# DieuKhienThietBiWinForm.net
KiCad netlist of a schematic drawn in Altium Designer
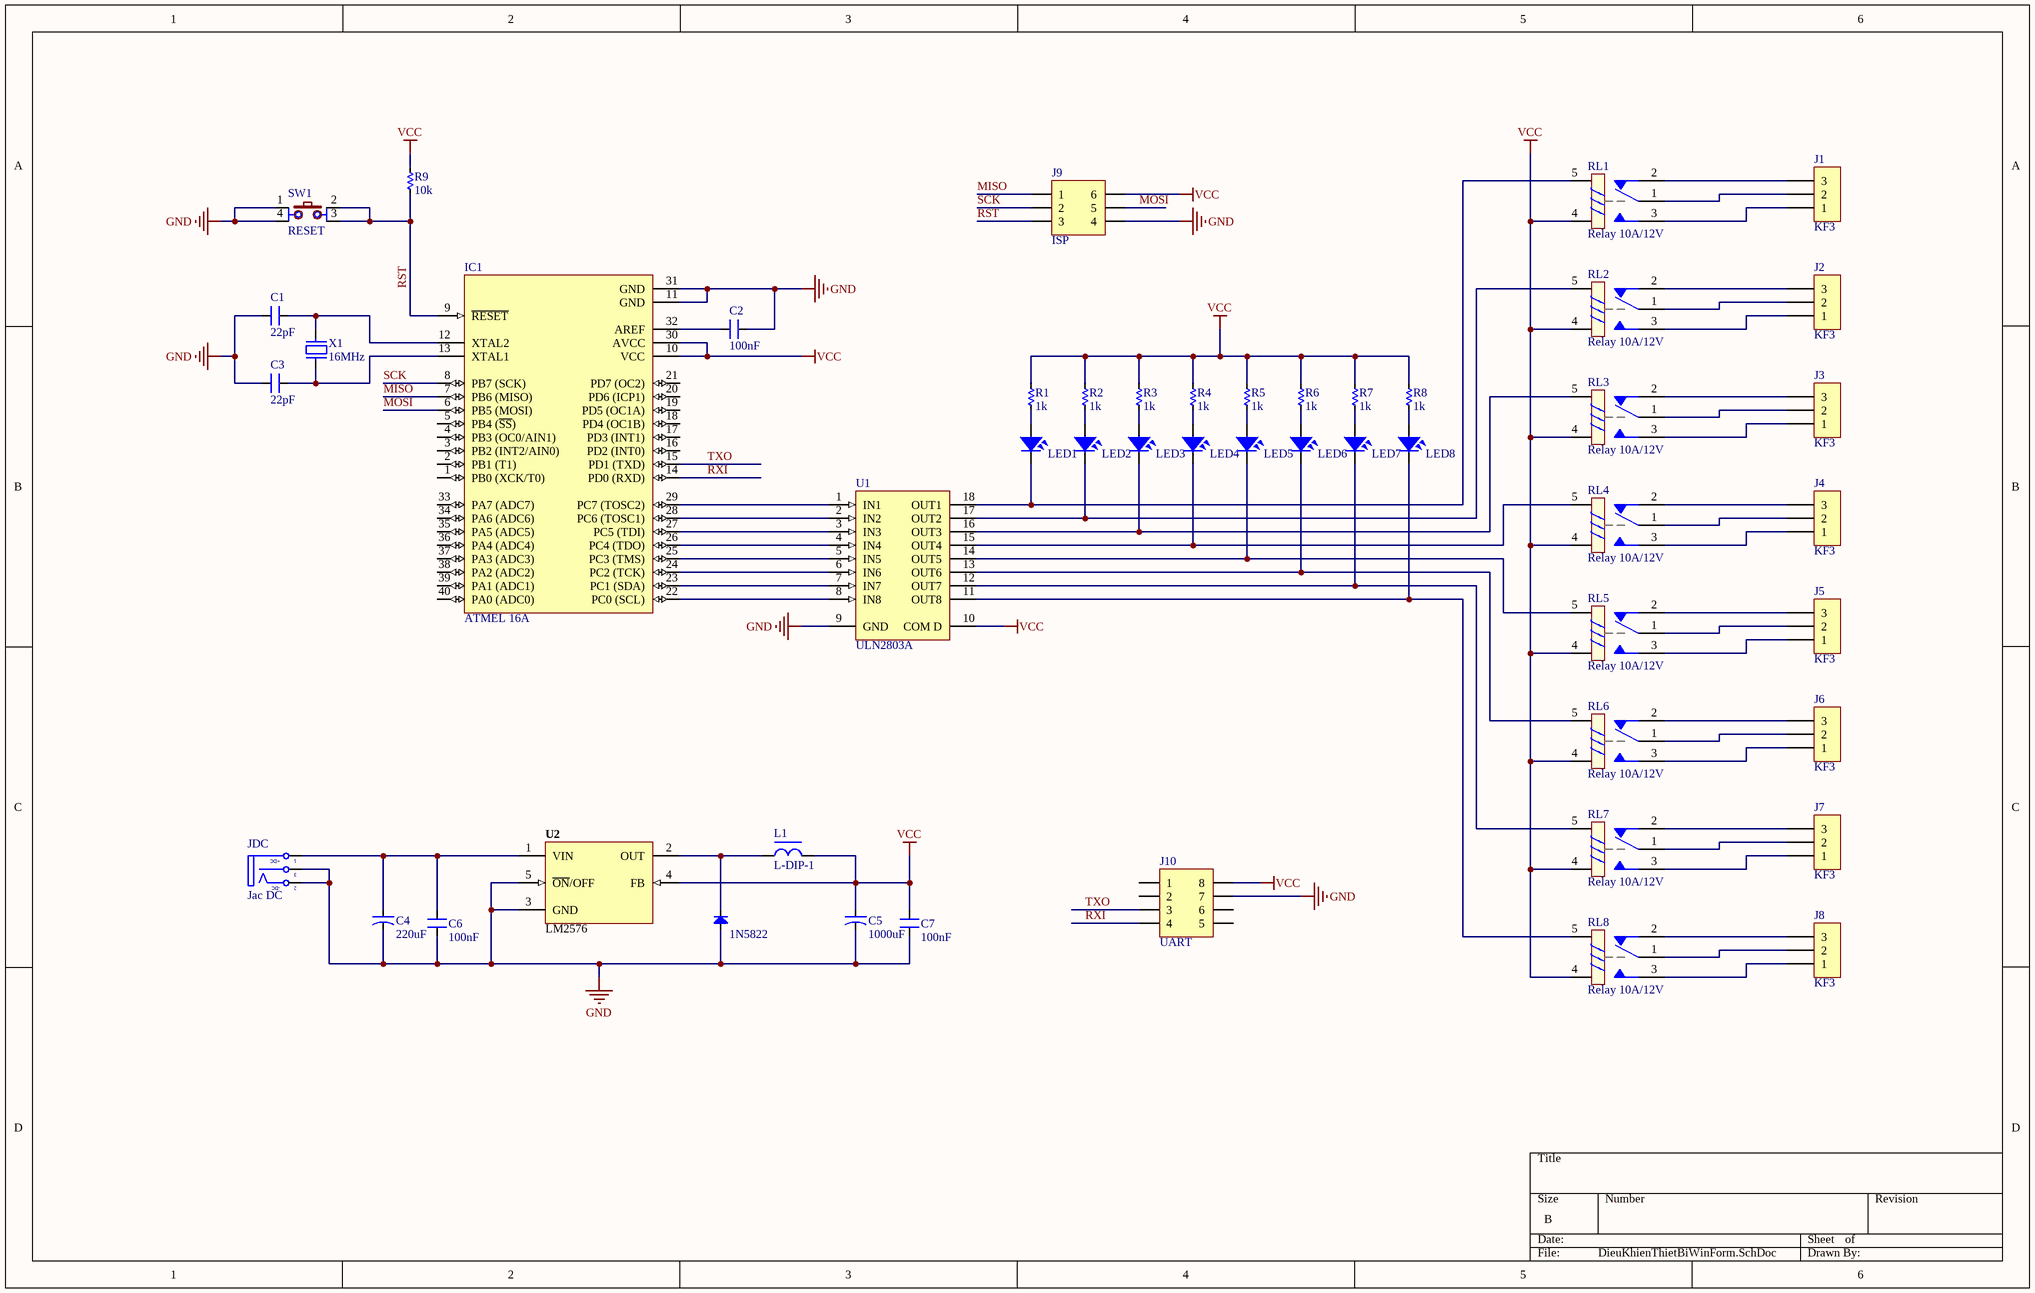
[diagram p0: DieuKhienThietBiWinForm.SchDoc]

(export (version "E")
  (design (tool "Eeschema 10.0.6"))
  (components
    (comp (ref "1N5822")
      (value "Diode")
      (footprint "DIO-5A")
      (description "Default Diode")
      (fields (field (name "PUBLISHER") "Altium Limited"))
      (libsource (lib "LIBRARY") (part "Diode"))
    )
    (comp (ref "C1") (value "22pF") (footprint "CN1.5") (libsource (lib "LIBRARY") (part "CN")))
    (comp (ref "C2") (value "100nF") (footprint "CN1.5") (libsource (lib "LIBRARY") (part "CN")))
    (comp (ref "C3") (value "22pF") (footprint "CN1.5") (libsource (lib "LIBRARY") (part "CN")))
    (comp (ref "C4")
      (value "220uF")
      (footprint "CA-ALU-8")
      (description "Capacitor (Semiconductor SIM Model)")
      (fields (field (name "PUBLISHER") "Altium Limited"))
      (libsource (lib "LIBRARY") (part "CN-ALU-DIP"))
    )
    (comp (ref "C5")
      (value "1000uF")
      (footprint "CA-ALU-10")
      (description "Capacitor (Semiconductor SIM Model)")
      (fields (field (name "PUBLISHER") "Altium Limited"))
      (libsource (lib "LIBRARY") (part "CN-ALU-DIP"))
    )
    (comp (ref "C6") (value "100nF") (footprint "CN1.5") (libsource (lib "LIBRARY") (part "CN")))
    (comp (ref "C7") (value "100nF") (footprint "CN1.5") (libsource (lib "LIBRARY") (part "CN")))
    (comp (ref "IC1")
      (value "ATMEL 16A")
      (footprint "DIP40/W0.6")
      (description "8-Bit AVR Microcontroller with 16K Bytes of In-System Programmable Flash Memory")
      (libsource (lib "LIBRARY") (part "ATmega16A-PU"))
    )
    (comp (ref "J1")
      (value "KF3")
      (footprint "KF3-5.08")
      (fields
        (field (name "MANUFACTURER") "Würth Elektronik eiSos GmbH")
        (field (name "PARTNO") "691103110003")
        (field (name "CREATED BY") "Karrer Zheng")
      )
      (libsource (lib "LIBRARY") (part "KF3"))
    )
    (comp (ref "J2")
      (value "KF3")
      (footprint "KF3-5.08")
      (fields
        (field (name "MANUFACTURER") "Würth Elektronik eiSos GmbH")
        (field (name "PARTNO") "691103110003")
        (field (name "CREATED BY") "Karrer Zheng")
      )
      (libsource (lib "LIBRARY") (part "KF3"))
    )
    (comp (ref "J3")
      (value "KF3")
      (footprint "KF3-5.08")
      (fields
        (field (name "MANUFACTURER") "Würth Elektronik eiSos GmbH")
        (field (name "PARTNO") "691103110003")
        (field (name "CREATED BY") "Karrer Zheng")
      )
      (libsource (lib "LIBRARY") (part "KF3"))
    )
    (comp (ref "J4")
      (value "KF3")
      (footprint "KF3-5.08")
      (fields
        (field (name "MANUFACTURER") "Würth Elektronik eiSos GmbH")
        (field (name "PARTNO") "691103110003")
        (field (name "CREATED BY") "Karrer Zheng")
      )
      (libsource (lib "LIBRARY") (part "KF3"))
    )
    (comp (ref "J5")
      (value "KF3")
      (footprint "KF3-5.08")
      (fields
        (field (name "MANUFACTURER") "Würth Elektronik eiSos GmbH")
        (field (name "PARTNO") "691103110003")
        (field (name "CREATED BY") "Karrer Zheng")
      )
      (libsource (lib "LIBRARY") (part "KF3"))
    )
    (comp (ref "J6")
      (value "KF3")
      (footprint "KF3-5.08")
      (fields
        (field (name "MANUFACTURER") "Würth Elektronik eiSos GmbH")
        (field (name "PARTNO") "691103110003")
        (field (name "CREATED BY") "Karrer Zheng")
      )
      (libsource (lib "LIBRARY") (part "KF3"))
    )
    (comp (ref "J7")
      (value "KF3")
      (footprint "KF3-5.08")
      (fields
        (field (name "MANUFACTURER") "Würth Elektronik eiSos GmbH")
        (field (name "PARTNO") "691103110003")
        (field (name "CREATED BY") "Karrer Zheng")
      )
      (libsource (lib "LIBRARY") (part "KF3"))
    )
    (comp (ref "J8")
      (value "KF3")
      (footprint "KF3-5.08")
      (fields
        (field (name "MANUFACTURER") "Würth Elektronik eiSos GmbH")
        (field (name "PARTNO") "691103110003")
        (field (name "CREATED BY") "Karrer Zheng")
      )
      (libsource (lib "LIBRARY") (part "KF3"))
    )
    (comp (ref "J9")
      (value "ISP")
      (footprint "JP3-D2T")
      (description "WR-PHD 2.54 mm Dual Socket Header")
      (fields
        (field (name "MANUFACTURER") "Würth Elektronik eiSos GmbH")
        (field (name "PARTNO") "61300621821")
        (field (name "CREATED BY") "Karrer Zheng")
      )
      (libsource (lib "LIBRARY") (part "JP3x2"))
    )
    (comp (ref "J10")
      (value "UART")
      (footprint "JP4-D2T")
      (description "WR-PHD 2.54 mm Dual Socket Header")
      (fields
        (field (name "MANUFACTURER") "Würth Elektronik eiSos GmbH")
        (field (name "PARTNO") "61300821821")
        (field (name "CREATED BY") "Karrer Zheng")
      )
      (libsource (lib "LIBRARY") (part "JP4x2"))
    )
    (comp (ref "JDC")
      (value "Jac DC")
      (footprint "DC0")
      (description "Jac DC input")
      (libsource (lib "LIBRARY") (part "DCIN"))
    )
    (comp (ref "L1")
      (value "L-DIP-1")
      (footprint "L-DIP-M-8")
      (description "Inductor")
      (libsource (lib "LIBRARY") (part "L-DIP-1"))
    )
    (comp (ref "LED1")
      (value "LED")
      (footprint "LED-5-RED")
      (description "LED Single colour Green and Red")
      (libsource (lib "LIBRARY") (part "LED"))
    )
    (comp (ref "LED2")
      (value "LED")
      (footprint "LED-5-RED")
      (description "LED Single colour Green and Red")
      (libsource (lib "LIBRARY") (part "LED"))
    )
    (comp (ref "LED3")
      (value "LED")
      (footprint "LED-5-RED")
      (description "LED Single colour Green and Red")
      (libsource (lib "LIBRARY") (part "LED"))
    )
    (comp (ref "LED4")
      (value "LED")
      (footprint "LED-5-RED")
      (description "LED Single colour Green and Red")
      (libsource (lib "LIBRARY") (part "LED"))
    )
    (comp (ref "LED5")
      (value "LED")
      (footprint "LED-5-RED")
      (description "LED Single colour Green and Red")
      (libsource (lib "LIBRARY") (part "LED"))
    )
    (comp (ref "LED6")
      (value "LED")
      (footprint "LED-5-RED")
      (description "LED Single colour Green and Red")
      (libsource (lib "LIBRARY") (part "LED"))
    )
    (comp (ref "LED7")
      (value "LED")
      (footprint "LED-5-RED")
      (description "LED Single colour Green and Red")
      (libsource (lib "LIBRARY") (part "LED"))
    )
    (comp (ref "LED8")
      (value "LED")
      (footprint "LED-5-RED")
      (description "LED Single colour Green and Red")
      (libsource (lib "LIBRARY") (part "LED"))
    )
    (comp (ref "R1")
      (value "1k")
      (footprint "RES-1/2W")
      (description "Res")
      (fields
        (field (name "MANUFACTURER") "Generic Components")
        (field (name "PUBLISHER") "Altium Hobart Technology Centre")
      )
      (libsource (lib "LIBRARY") (part "Res"))
    )
    (comp (ref "R2")
      (value "1k")
      (footprint "RES-1/2W")
      (description "Res")
      (fields
        (field (name "MANUFACTURER") "Generic Components")
        (field (name "PUBLISHER") "Altium Hobart Technology Centre")
      )
      (libsource (lib "LIBRARY") (part "Res"))
    )
    (comp (ref "R3")
      (value "1k")
      (footprint "RES-1/2W")
      (description "Res")
      (fields
        (field (name "MANUFACTURER") "Generic Components")
        (field (name "PUBLISHER") "Altium Hobart Technology Centre")
      )
      (libsource (lib "LIBRARY") (part "Res"))
    )
    (comp (ref "R4")
      (value "1k")
      (footprint "RES-1/2W")
      (description "Res")
      (fields
        (field (name "MANUFACTURER") "Generic Components")
        (field (name "PUBLISHER") "Altium Hobart Technology Centre")
      )
      (libsource (lib "LIBRARY") (part "Res"))
    )
    (comp (ref "R5")
      (value "1k")
      (footprint "RES-1/2W")
      (description "Res")
      (fields
        (field (name "MANUFACTURER") "Generic Components")
        (field (name "PUBLISHER") "Altium Hobart Technology Centre")
      )
      (libsource (lib "LIBRARY") (part "Res"))
    )
    (comp (ref "R6")
      (value "1k")
      (footprint "RES-1/2W")
      (description "Res")
      (fields
        (field (name "MANUFACTURER") "Generic Components")
        (field (name "PUBLISHER") "Altium Hobart Technology Centre")
      )
      (libsource (lib "LIBRARY") (part "Res"))
    )
    (comp (ref "R7")
      (value "1k")
      (footprint "RES-1/2W")
      (description "Res")
      (fields
        (field (name "MANUFACTURER") "Generic Components")
        (field (name "PUBLISHER") "Altium Hobart Technology Centre")
      )
      (libsource (lib "LIBRARY") (part "Res"))
    )
    (comp (ref "R8")
      (value "1k")
      (footprint "RES-1/2W")
      (description "Res")
      (fields
        (field (name "MANUFACTURER") "Generic Components")
        (field (name "PUBLISHER") "Altium Hobart Technology Centre")
      )
      (libsource (lib "LIBRARY") (part "Res"))
    )
    (comp (ref "R9")
      (value "10k")
      (footprint "RES-1/2W")
      (description "Res")
      (fields
        (field (name "MANUFACTURER") "Generic Components")
        (field (name "PUBLISHER") "Altium Hobart Technology Centre")
      )
      (libsource (lib "LIBRARY") (part "Res"))
    )
    (comp (ref "RL1")
      (value "Relay 10A/12V")
      (footprint "RELAY 5")
      (description "Relay SPDT,10A - 12VDC 5 Pin")
      (libsource (lib "LIBRARY") (part "Relay 5"))
    )
    (comp (ref "RL2")
      (value "Relay 10A/12V")
      (footprint "RELAY 5")
      (description "Relay SPDT,10A - 12VDC 5 Pin")
      (libsource (lib "LIBRARY") (part "Relay 5"))
    )
    (comp (ref "RL3")
      (value "Relay 10A/12V")
      (footprint "RELAY 5")
      (description "Relay SPDT,10A - 12VDC 5 Pin")
      (libsource (lib "LIBRARY") (part "Relay 5"))
    )
    (comp (ref "RL4")
      (value "Relay 10A/12V")
      (footprint "RELAY 5")
      (description "Relay SPDT,10A - 12VDC 5 Pin")
      (libsource (lib "LIBRARY") (part "Relay 5"))
    )
    (comp (ref "RL5")
      (value "Relay 10A/12V")
      (footprint "RELAY 5")
      (description "Relay SPDT,10A - 12VDC 5 Pin")
      (libsource (lib "LIBRARY") (part "Relay 5"))
    )
    (comp (ref "RL6")
      (value "Relay 10A/12V")
      (footprint "RELAY 5")
      (description "Relay SPDT,10A - 12VDC 5 Pin")
      (libsource (lib "LIBRARY") (part "Relay 5"))
    )
    (comp (ref "RL7")
      (value "Relay 10A/12V")
      (footprint "RELAY 5")
      (description "Relay SPDT,10A - 12VDC 5 Pin")
      (libsource (lib "LIBRARY") (part "Relay 5"))
    )
    (comp (ref "RL8")
      (value "Relay 10A/12V")
      (footprint "RELAY 5")
      (description "Relay SPDT,10A - 12VDC 5 Pin")
      (libsource (lib "LIBRARY") (part "Relay 5"))
    )
    (comp (ref "SW1")
      (value "RESET")
      (footprint "SW2-DIP")
      (description "Switch button 4 pin")
      (libsource (lib "LIBRARY") (part "SW4"))
    )
    (comp (ref "U1")
      (value "ULN2803A")
      (footprint "DIP18")
      (description "High-Voltage, High-Current Darlington Array")
      (fields (field (name "PUBLISHER") "Altium Limited"))
      (libsource (lib "LIBRARY") (part "ULN2803A"))
    )
    (comp (ref "U2") (value "LM2576") (footprint "DIP5") (libsource (lib "LIBRARY") (part "LM2576")))
    (comp (ref "X1")
      (value "16MHz")
      (footprint "XT2")
      (description "Crystal, 32.768 KHz, -40 to 85 degC, 3.2 x 1.5 x 0.9 mm SMD")
      (libsource (lib "LIBRARY") (part "XT2"))
    )
  )
  (nets
    (net (code "1") (name "/MISO") (class "Default")
      (node (ref "IC1") (pin "7") (pinfunction "PB6_(MISO)_7") (pintype "bidirectional"))
      (node (ref "J9") (pin "1") (pinfunction "1_1") (pintype "passive"))
    )
    (net (code "2") (name "/MOSI") (class "Default")
      (node (ref "IC1") (pin "6") (pinfunction "PB5_(MOSI)_6") (pintype "bidirectional"))
      (node (ref "J9") (pin "5") (pinfunction "5_5") (pintype "passive"))
    )
    (net (code "3") (name "/RST") (class "Default")
      (node (ref "IC1") (pin "9") (pinfunction "~{RESET}_9") (pintype "input"))
      (node (ref "J9") (pin "3") (pinfunction "3_3") (pintype "passive"))
      (node (ref "R9") (pin "1") (pinfunction "1_1") (pintype "passive"))
      (node (ref "SW1") (pin "2") (pinfunction "2_2") (pintype "passive"))
      (node (ref "SW1") (pin "3") (pinfunction "3_3") (pintype "passive"))
    )
    (net (code "4") (name "/RXI") (class "Default")
      (node (ref "IC1") (pin "14") (pinfunction "PD0_(RXD)_14") (pintype "bidirectional"))
      (node (ref "J10") (pin "4") (pinfunction "4_4") (pintype "passive"))
    )
    (net (code "5") (name "/SCK") (class "Default")
      (node (ref "IC1") (pin "8") (pinfunction "PB7_(SCK)_8") (pintype "bidirectional"))
      (node (ref "J9") (pin "2") (pinfunction "2_2") (pintype "passive"))
    )
    (net (code "6") (name "/TXO") (class "Default")
      (node (ref "IC1") (pin "15") (pinfunction "PD1_(TXD)_15") (pintype "bidirectional"))
      (node (ref "J10") (pin "3") (pinfunction "3_3") (pintype "passive"))
    )
    (net (code "7") (name "GND") (class "Default")
      (node (ref "1N5822") (pin "1") (pinfunction "A_1") (pintype "passive"))
      (node (ref "C1") (pin "1") (pinfunction "1_1") (pintype "passive"))
      (node (ref "C2") (pin "2") (pinfunction "2_2") (pintype "passive"))
      (node (ref "C3") (pin "1") (pinfunction "1_1") (pintype "passive"))
      (node (ref "C4") (pin "2") (pinfunction "2_2") (pintype "passive"))
      (node (ref "C5") (pin "2") (pinfunction "2_2") (pintype "passive"))
      (node (ref "C6") (pin "1") (pinfunction "1_1") (pintype "passive"))
      (node (ref "C7") (pin "1") (pinfunction "1_1") (pintype "passive"))
      (node (ref "IC1") (pin "11") (pinfunction "GND_11") (pintype "power_in"))
      (node (ref "IC1") (pin "31") (pinfunction "GND_31") (pintype "power_in"))
      (node (ref "J10") (pin "7") (pinfunction "7_7") (pintype "passive"))
      (node (ref "J9") (pin "4") (pinfunction "4_4") (pintype "passive"))
      (node (ref "JDC") (pin "2") (pinfunction "TN_2") (pintype "passive"))
      (node (ref "JDC") (pin "3") (pinfunction "S_3") (pintype "power_in"))
      (node (ref "SW1") (pin "1") (pintype "passive"))
      (node (ref "SW1") (pin "4") (pinfunction "4_4") (pintype "passive"))
      (node (ref "U1") (pin "9") (pinfunction "GND_9") (pintype "power_in"))
      (node (ref "U2") (pin "3") (pinfunction "GND_3") (pintype "power_in"))
      (node (ref "U2") (pin "5") (pinfunction "~{ON}/OFF_5") (pintype "input"))
    )
    (net (code "8") (name "Net-(1N5822-K)") (class "Default")
      (node (ref "1N5822") (pin "2") (pinfunction "K_2") (pintype "passive"))
      (node (ref "L1") (pin "1") (pinfunction "1_1") (pintype "passive"))
      (node (ref "U2") (pin "2") (pinfunction "OUT_2") (pintype "power_in"))
    )
    (net (code "9") (name "Net-(IC1-AREF)") (class "Default")
      (node (ref "C2") (pin "1") (pinfunction "1_1") (pintype "passive"))
      (node (ref "IC1") (pin "32") (pinfunction "AREF_32") (pintype "power_in"))
    )
    (net (code "10") (name "Net-(IC1-PC0_(SCL))") (class "Default")
      (node (ref "IC1") (pin "22") (pinfunction "PC0_(SCL)_22") (pintype "bidirectional"))
      (node (ref "U1") (pin "8") (pinfunction "IN8_8") (pintype "input"))
    )
    (net (code "11") (name "Net-(IC1-PC1_(SDA))") (class "Default")
      (node (ref "IC1") (pin "23") (pinfunction "PC1_(SDA)_23") (pintype "bidirectional"))
      (node (ref "U1") (pin "7") (pinfunction "IN7_7") (pintype "input"))
    )
    (net (code "12") (name "Net-(IC1-PC2_(TCK))") (class "Default")
      (node (ref "IC1") (pin "24") (pinfunction "PC2_(TCK)_24") (pintype "bidirectional"))
      (node (ref "U1") (pin "6") (pinfunction "IN6_6") (pintype "input"))
    )
    (net (code "13") (name "Net-(IC1-PC3_(TMS))") (class "Default")
      (node (ref "IC1") (pin "25") (pinfunction "PC3_(TMS)_25") (pintype "bidirectional"))
      (node (ref "U1") (pin "5") (pinfunction "IN5_5") (pintype "input"))
    )
    (net (code "14") (name "Net-(IC1-PC4_(TDO))") (class "Default")
      (node (ref "IC1") (pin "26") (pinfunction "PC4_(TDO)_26") (pintype "bidirectional"))
      (node (ref "U1") (pin "4") (pinfunction "IN4_4") (pintype "input"))
    )
    (net (code "15") (name "Net-(IC1-PC5_(TDI))") (class "Default")
      (node (ref "IC1") (pin "27") (pinfunction "PC5_(TDI)_27") (pintype "bidirectional"))
      (node (ref "U1") (pin "3") (pinfunction "IN3_3") (pintype "input"))
    )
    (net (code "16") (name "Net-(IC1-PC6_(TOSC1))") (class "Default")
      (node (ref "IC1") (pin "28") (pinfunction "PC6_(TOSC1)_28") (pintype "bidirectional"))
      (node (ref "U1") (pin "2") (pinfunction "IN2_2") (pintype "input"))
    )
    (net (code "17") (name "Net-(IC1-PC7_(TOSC2))") (class "Default")
      (node (ref "IC1") (pin "29") (pinfunction "PC7_(TOSC2)_29") (pintype "bidirectional"))
      (node (ref "U1") (pin "1") (pinfunction "IN1_1") (pintype "input"))
    )
    (net (code "18") (name "Net-(IC1-XTAL1)") (class "Default")
      (node (ref "C3") (pin "2") (pinfunction "2_2") (pintype "passive"))
      (node (ref "IC1") (pin "13") (pinfunction "XTAL1_13") (pintype "passive"))
      (node (ref "X1") (pin "2") (pinfunction "2_2") (pintype "passive"))
    )
    (net (code "19") (name "Net-(IC1-XTAL2)") (class "Default")
      (node (ref "C1") (pin "2") (pinfunction "2_2") (pintype "passive"))
      (node (ref "IC1") (pin "12") (pinfunction "XTAL2_12") (pintype "passive"))
      (node (ref "X1") (pin "1") (pinfunction "1_1") (pintype "passive"))
    )
    (net (code "20") (name "Net-(J1-Pad1)") (class "Default")
      (node (ref "J1") (pin "1") (pinfunction "1_1") (pintype "passive"))
      (node (ref "RL1") (pin "3") (pinfunction "3_3") (pintype "passive"))
    )
    (net (code "21") (name "Net-(J1-Pad2)") (class "Default")
      (node (ref "J1") (pin "2") (pinfunction "2_2") (pintype "passive"))
      (node (ref "RL1") (pin "1") (pinfunction "1_1") (pintype "passive"))
    )
    (net (code "22") (name "Net-(J1-Pad3)") (class "Default")
      (node (ref "J1") (pin "3") (pinfunction "3_3") (pintype "passive"))
      (node (ref "RL1") (pin "2") (pinfunction "2_2") (pintype "passive"))
    )
    (net (code "23") (name "Net-(J2-Pad1)") (class "Default")
      (node (ref "J2") (pin "1") (pinfunction "1_1") (pintype "passive"))
      (node (ref "RL2") (pin "3") (pinfunction "3_3") (pintype "passive"))
    )
    (net (code "24") (name "Net-(J2-Pad2)") (class "Default")
      (node (ref "J2") (pin "2") (pinfunction "2_2") (pintype "passive"))
      (node (ref "RL2") (pin "1") (pinfunction "1_1") (pintype "passive"))
    )
    (net (code "25") (name "Net-(J2-Pad3)") (class "Default")
      (node (ref "J2") (pin "3") (pinfunction "3_3") (pintype "passive"))
      (node (ref "RL2") (pin "2") (pinfunction "2_2") (pintype "passive"))
    )
    (net (code "26") (name "Net-(J3-Pad1)") (class "Default")
      (node (ref "J3") (pin "1") (pinfunction "1_1") (pintype "passive"))
      (node (ref "RL3") (pin "3") (pinfunction "3_3") (pintype "passive"))
    )
    (net (code "27") (name "Net-(J3-Pad2)") (class "Default")
      (node (ref "J3") (pin "2") (pinfunction "2_2") (pintype "passive"))
      (node (ref "RL3") (pin "1") (pinfunction "1_1") (pintype "passive"))
    )
    (net (code "28") (name "Net-(J3-Pad3)") (class "Default")
      (node (ref "J3") (pin "3") (pinfunction "3_3") (pintype "passive"))
      (node (ref "RL3") (pin "2") (pinfunction "2_2") (pintype "passive"))
    )
    (net (code "29") (name "Net-(J4-Pad1)") (class "Default")
      (node (ref "J4") (pin "1") (pinfunction "1_1") (pintype "passive"))
      (node (ref "RL4") (pin "3") (pinfunction "3_3") (pintype "passive"))
    )
    (net (code "30") (name "Net-(J4-Pad2)") (class "Default")
      (node (ref "J4") (pin "2") (pinfunction "2_2") (pintype "passive"))
      (node (ref "RL4") (pin "1") (pinfunction "1_1") (pintype "passive"))
    )
    (net (code "31") (name "Net-(J4-Pad3)") (class "Default")
      (node (ref "J4") (pin "3") (pinfunction "3_3") (pintype "passive"))
      (node (ref "RL4") (pin "2") (pinfunction "2_2") (pintype "passive"))
    )
    (net (code "32") (name "Net-(J5-Pad1)") (class "Default")
      (node (ref "J5") (pin "1") (pinfunction "1_1") (pintype "passive"))
      (node (ref "RL5") (pin "3") (pinfunction "3_3") (pintype "passive"))
    )
    (net (code "33") (name "Net-(J5-Pad2)") (class "Default")
      (node (ref "J5") (pin "2") (pinfunction "2_2") (pintype "passive"))
      (node (ref "RL5") (pin "1") (pinfunction "1_1") (pintype "passive"))
    )
    (net (code "34") (name "Net-(J5-Pad3)") (class "Default")
      (node (ref "J5") (pin "3") (pinfunction "3_3") (pintype "passive"))
      (node (ref "RL5") (pin "2") (pinfunction "2_2") (pintype "passive"))
    )
    (net (code "35") (name "Net-(J6-Pad1)") (class "Default")
      (node (ref "J6") (pin "1") (pinfunction "1_1") (pintype "passive"))
      (node (ref "RL6") (pin "3") (pinfunction "3_3") (pintype "passive"))
    )
    (net (code "36") (name "Net-(J6-Pad2)") (class "Default")
      (node (ref "J6") (pin "2") (pinfunction "2_2") (pintype "passive"))
      (node (ref "RL6") (pin "1") (pinfunction "1_1") (pintype "passive"))
    )
    (net (code "37") (name "Net-(J6-Pad3)") (class "Default")
      (node (ref "J6") (pin "3") (pinfunction "3_3") (pintype "passive"))
      (node (ref "RL6") (pin "2") (pinfunction "2_2") (pintype "passive"))
    )
    (net (code "38") (name "Net-(J7-Pad1)") (class "Default")
      (node (ref "J7") (pin "1") (pinfunction "1_1") (pintype "passive"))
      (node (ref "RL7") (pin "3") (pinfunction "3_3") (pintype "passive"))
    )
    (net (code "39") (name "Net-(J7-Pad2)") (class "Default")
      (node (ref "J7") (pin "2") (pinfunction "2_2") (pintype "passive"))
      (node (ref "RL7") (pin "1") (pinfunction "1_1") (pintype "passive"))
    )
    (net (code "40") (name "Net-(J7-Pad3)") (class "Default")
      (node (ref "J7") (pin "3") (pinfunction "3_3") (pintype "passive"))
      (node (ref "RL7") (pin "2") (pinfunction "2_2") (pintype "passive"))
    )
    (net (code "41") (name "Net-(J8-Pad1)") (class "Default")
      (node (ref "J8") (pin "1") (pinfunction "1_1") (pintype "passive"))
      (node (ref "RL8") (pin "3") (pinfunction "3_3") (pintype "passive"))
    )
    (net (code "42") (name "Net-(J8-Pad2)") (class "Default")
      (node (ref "J8") (pin "2") (pinfunction "2_2") (pintype "passive"))
      (node (ref "RL8") (pin "1") (pinfunction "1_1") (pintype "passive"))
    )
    (net (code "43") (name "Net-(J8-Pad3)") (class "Default")
      (node (ref "J8") (pin "3") (pinfunction "3_3") (pintype "passive"))
      (node (ref "RL8") (pin "2") (pinfunction "2_2") (pintype "passive"))
    )
    (net (code "44") (name "Net-(JDC-T)") (class "Default")
      (node (ref "C4") (pin "1") (pinfunction "1_1") (pintype "passive"))
      (node (ref "C6") (pin "2") (pinfunction "2_2") (pintype "passive"))
      (node (ref "JDC") (pin "1") (pinfunction "T_1") (pintype "passive"))
      (node (ref "U2") (pin "1") (pinfunction "VIN_1") (pintype "power_in"))
    )
    (net (code "45") (name "Net-(LED1-Pad1)") (class "Default")
      (node (ref "LED1") (pin "1") (pinfunction "1_1") (pintype "passive"))
      (node (ref "R1") (pin "1") (pinfunction "1_1") (pintype "passive"))
    )
    (net (code "46") (name "Net-(LED2-Pad1)") (class "Default")
      (node (ref "LED2") (pin "1") (pinfunction "1_1") (pintype "passive"))
      (node (ref "R2") (pin "1") (pinfunction "1_1") (pintype "passive"))
    )
    (net (code "47") (name "Net-(LED3-Pad1)") (class "Default")
      (node (ref "LED3") (pin "1") (pinfunction "1_1") (pintype "passive"))
      (node (ref "R3") (pin "1") (pinfunction "1_1") (pintype "passive"))
    )
    (net (code "48") (name "Net-(LED4-Pad1)") (class "Default")
      (node (ref "LED4") (pin "1") (pinfunction "1_1") (pintype "passive"))
      (node (ref "R4") (pin "1") (pinfunction "1_1") (pintype "passive"))
    )
    (net (code "49") (name "Net-(LED5-Pad1)") (class "Default")
      (node (ref "LED5") (pin "1") (pinfunction "1_1") (pintype "passive"))
      (node (ref "R5") (pin "1") (pinfunction "1_1") (pintype "passive"))
    )
    (net (code "50") (name "Net-(LED6-Pad1)") (class "Default")
      (node (ref "LED6") (pin "1") (pinfunction "1_1") (pintype "passive"))
      (node (ref "R6") (pin "1") (pinfunction "1_1") (pintype "passive"))
    )
    (net (code "51") (name "Net-(LED7-Pad1)") (class "Default")
      (node (ref "LED7") (pin "1") (pinfunction "1_1") (pintype "passive"))
      (node (ref "R7") (pin "1") (pinfunction "1_1") (pintype "passive"))
    )
    (net (code "52") (name "Net-(LED8-Pad1)") (class "Default")
      (node (ref "LED8") (pin "1") (pinfunction "1_1") (pintype "passive"))
      (node (ref "R8") (pin "1") (pinfunction "1_1") (pintype "passive"))
    )
    (net (code "53") (name "Net-(U1-OUT1)") (class "Default")
      (node (ref "LED1") (pin "2") (pinfunction "2_2") (pintype "passive"))
      (node (ref "RL1") (pin "5") (pinfunction "5_5") (pintype "passive"))
      (node (ref "U1") (pin "18") (pinfunction "OUT1_18") (pintype "open_collector"))
    )
    (net (code "54") (name "Net-(U1-OUT2)") (class "Default")
      (node (ref "LED2") (pin "2") (pinfunction "2_2") (pintype "passive"))
      (node (ref "RL2") (pin "5") (pinfunction "5_5") (pintype "passive"))
      (node (ref "U1") (pin "17") (pinfunction "OUT2_17") (pintype "open_collector"))
    )
    (net (code "55") (name "Net-(U1-OUT3)") (class "Default")
      (node (ref "LED3") (pin "2") (pinfunction "2_2") (pintype "passive"))
      (node (ref "RL3") (pin "5") (pinfunction "5_5") (pintype "passive"))
      (node (ref "U1") (pin "16") (pinfunction "OUT3_16") (pintype "open_collector"))
    )
    (net (code "56") (name "Net-(U1-OUT4)") (class "Default")
      (node (ref "LED4") (pin "2") (pinfunction "2_2") (pintype "passive"))
      (node (ref "RL4") (pin "5") (pinfunction "5_5") (pintype "passive"))
      (node (ref "U1") (pin "15") (pinfunction "OUT4_15") (pintype "open_collector"))
    )
    (net (code "57") (name "Net-(U1-OUT5)") (class "Default")
      (node (ref "LED5") (pin "2") (pinfunction "2_2") (pintype "passive"))
      (node (ref "RL5") (pin "5") (pinfunction "5_5") (pintype "passive"))
      (node (ref "U1") (pin "14") (pinfunction "OUT5_14") (pintype "open_collector"))
    )
    (net (code "58") (name "Net-(U1-OUT6)") (class "Default")
      (node (ref "LED6") (pin "2") (pinfunction "2_2") (pintype "passive"))
      (node (ref "RL6") (pin "5") (pinfunction "5_5") (pintype "passive"))
      (node (ref "U1") (pin "13") (pinfunction "OUT6_13") (pintype "open_collector"))
    )
    (net (code "59") (name "Net-(U1-OUT7)") (class "Default")
      (node (ref "LED7") (pin "2") (pinfunction "2_2") (pintype "passive"))
      (node (ref "RL7") (pin "5") (pinfunction "5_5") (pintype "passive"))
      (node (ref "U1") (pin "12") (pinfunction "OUT7_12") (pintype "open_collector"))
    )
    (net (code "60") (name "Net-(U1-OUT8)") (class "Default")
      (node (ref "LED8") (pin "2") (pinfunction "2_2") (pintype "passive"))
      (node (ref "RL8") (pin "5") (pinfunction "5_5") (pintype "passive"))
      (node (ref "U1") (pin "11") (pinfunction "OUT8_11") (pintype "open_collector"))
    )
    (net (code "61") (name "VCC") (class "Default")
      (node (ref "C5") (pin "1") (pinfunction "1_1") (pintype "passive"))
      (node (ref "C7") (pin "2") (pinfunction "2_2") (pintype "passive"))
      (node (ref "IC1") (pin "10") (pinfunction "VCC_10") (pintype "power_in"))
      (node (ref "IC1") (pin "30") (pinfunction "AVCC_30") (pintype "power_in"))
      (node (ref "J10") (pin "8") (pinfunction "8_8") (pintype "passive"))
      (node (ref "J9") (pin "6") (pinfunction "6_6") (pintype "passive"))
      (node (ref "L1") (pin "2") (pinfunction "2_2") (pintype "passive"))
      (node (ref "R1") (pin "2") (pinfunction "2_2") (pintype "passive"))
      (node (ref "R2") (pin "2") (pinfunction "2_2") (pintype "passive"))
      (node (ref "R3") (pin "2") (pinfunction "2_2") (pintype "passive"))
      (node (ref "R4") (pin "2") (pinfunction "2_2") (pintype "passive"))
      (node (ref "R5") (pin "2") (pinfunction "2_2") (pintype "passive"))
      (node (ref "R6") (pin "2") (pinfunction "2_2") (pintype "passive"))
      (node (ref "R7") (pin "2") (pinfunction "2_2") (pintype "passive"))
      (node (ref "R8") (pin "2") (pinfunction "2_2") (pintype "passive"))
      (node (ref "R9") (pin "2") (pinfunction "2_2") (pintype "passive"))
      (node (ref "RL1") (pin "4") (pinfunction "4_4") (pintype "passive"))
      (node (ref "RL2") (pin "4") (pinfunction "4_4") (pintype "passive"))
      (node (ref "RL3") (pin "4") (pinfunction "4_4") (pintype "passive"))
      (node (ref "RL4") (pin "4") (pinfunction "4_4") (pintype "passive"))
      (node (ref "RL5") (pin "4") (pinfunction "4_4") (pintype "passive"))
      (node (ref "RL6") (pin "4") (pinfunction "4_4") (pintype "passive"))
      (node (ref "RL7") (pin "4") (pinfunction "4_4") (pintype "passive"))
      (node (ref "RL8") (pin "4") (pinfunction "4_4") (pintype "passive"))
      (node (ref "U1") (pin "10") (pinfunction "COM_D_10") (pintype "passive"))
      (node (ref "U2") (pin "4") (pinfunction "FB_4") (pintype "input"))
    )
    (net (code "62") (name "unconnected-(IC1-PA0_(ADC0)-Pad40)") (class "Default")
      (node (ref "IC1") (pin "40") (pinfunction "PA0_(ADC0)_40") (pintype "bidirectional"))
    )
    (net (code "63") (name "unconnected-(IC1-PA1_(ADC1)-Pad39)") (class "Default")
      (node (ref "IC1") (pin "39") (pinfunction "PA1_(ADC1)_39") (pintype "bidirectional"))
    )
    (net (code "64") (name "unconnected-(IC1-PA2_(ADC2)-Pad38)") (class "Default")
      (node (ref "IC1") (pin "38") (pinfunction "PA2_(ADC2)_38") (pintype "bidirectional"))
    )
    (net (code "65") (name "unconnected-(IC1-PA3_(ADC3)-Pad37)") (class "Default")
      (node (ref "IC1") (pin "37") (pinfunction "PA3_(ADC3)_37") (pintype "bidirectional"))
    )
    (net (code "66") (name "unconnected-(IC1-PA4_(ADC4)-Pad36)") (class "Default")
      (node (ref "IC1") (pin "36") (pinfunction "PA4_(ADC4)_36") (pintype "bidirectional"))
    )
    (net (code "67") (name "unconnected-(IC1-PA5_(ADC5)-Pad35)") (class "Default")
      (node (ref "IC1") (pin "35") (pinfunction "PA5_(ADC5)_35") (pintype "bidirectional"))
    )
    (net (code "68") (name "unconnected-(IC1-PA6_(ADC6)-Pad34)") (class "Default")
      (node (ref "IC1") (pin "34") (pinfunction "PA6_(ADC6)_34") (pintype "bidirectional"))
    )
    (net (code "69") (name "unconnected-(IC1-PA7_(ADC7)-Pad33)") (class "Default")
      (node (ref "IC1") (pin "33") (pinfunction "PA7_(ADC7)_33") (pintype "bidirectional"))
    )
    (net (code "70") (name "unconnected-(IC1-PB0_(XCK{slash}T0)-Pad1)") (class "Default")
      (node (ref "IC1") (pin "1") (pinfunction "PB0_(XCK/T0)_1") (pintype "bidirectional"))
    )
    (net (code "71") (name "unconnected-(IC1-PB1_(T1)-Pad2)") (class "Default")
      (node (ref "IC1") (pin "2") (pinfunction "PB1_(T1)_2") (pintype "bidirectional"))
    )
    (net (code "72") (name "unconnected-(IC1-PB2_(INT2{slash}AIN0)-Pad3)") (class "Default")
      (node (ref "IC1") (pin "3") (pinfunction "PB2_(INT2/AIN0)_3") (pintype "bidirectional"))
    )
    (net (code "73") (name "unconnected-(IC1-PB3_(OC0{slash}AIN1)-Pad4)") (class "Default")
      (node (ref "IC1") (pin "4") (pinfunction "PB3_(OC0/AIN1)_4") (pintype "bidirectional"))
    )
    (net (code "74") (name "unconnected-(IC1-PB4_(~{SS})-Pad5)") (class "Default")
      (node (ref "IC1") (pin "5") (pinfunction "PB4_(~{SS})_5") (pintype "bidirectional"))
    )
    (net (code "75") (name "unconnected-(IC1-PD2_(INT0)-Pad16)") (class "Default")
      (node (ref "IC1") (pin "16") (pinfunction "PD2_(INT0)_16") (pintype "bidirectional"))
    )
    (net (code "76") (name "unconnected-(IC1-PD3_(INT1)-Pad17)") (class "Default")
      (node (ref "IC1") (pin "17") (pinfunction "PD3_(INT1)_17") (pintype "bidirectional"))
    )
    (net (code "77") (name "unconnected-(IC1-PD4_(OC1B)-Pad18)") (class "Default")
      (node (ref "IC1") (pin "18") (pinfunction "PD4_(OC1B)_18") (pintype "bidirectional"))
    )
    (net (code "78") (name "unconnected-(IC1-PD5_(OC1A)-Pad19)") (class "Default")
      (node (ref "IC1") (pin "19") (pinfunction "PD5_(OC1A)_19") (pintype "bidirectional"))
    )
    (net (code "79") (name "unconnected-(IC1-PD6_(ICP1)-Pad20)") (class "Default")
      (node (ref "IC1") (pin "20") (pinfunction "PD6_(ICP1)_20") (pintype "bidirectional"))
    )
    (net (code "80") (name "unconnected-(IC1-PD7_(OC2)-Pad21)") (class "Default")
      (node (ref "IC1") (pin "21") (pinfunction "PD7_(OC2)_21") (pintype "bidirectional"))
    )
    (net (code "81") (name "unconnected-(J10-Pad1)") (class "Default")
      (node (ref "J10") (pin "1") (pinfunction "1_1") (pintype "passive"))
    )
    (net (code "82") (name "unconnected-(J10-Pad2)") (class "Default")
      (node (ref "J10") (pin "2") (pinfunction "2_2") (pintype "passive"))
    )
    (net (code "83") (name "unconnected-(J10-Pad5)") (class "Default")
      (node (ref "J10") (pin "5") (pinfunction "5_5") (pintype "passive"))
    )
    (net (code "84") (name "unconnected-(J10-Pad6)") (class "Default")
      (node (ref "J10") (pin "6") (pinfunction "6_6") (pintype "passive"))
    )
  )
)
